# motorControllerMk3.net
KiCad netlist of a schematic drawn in EAGLE
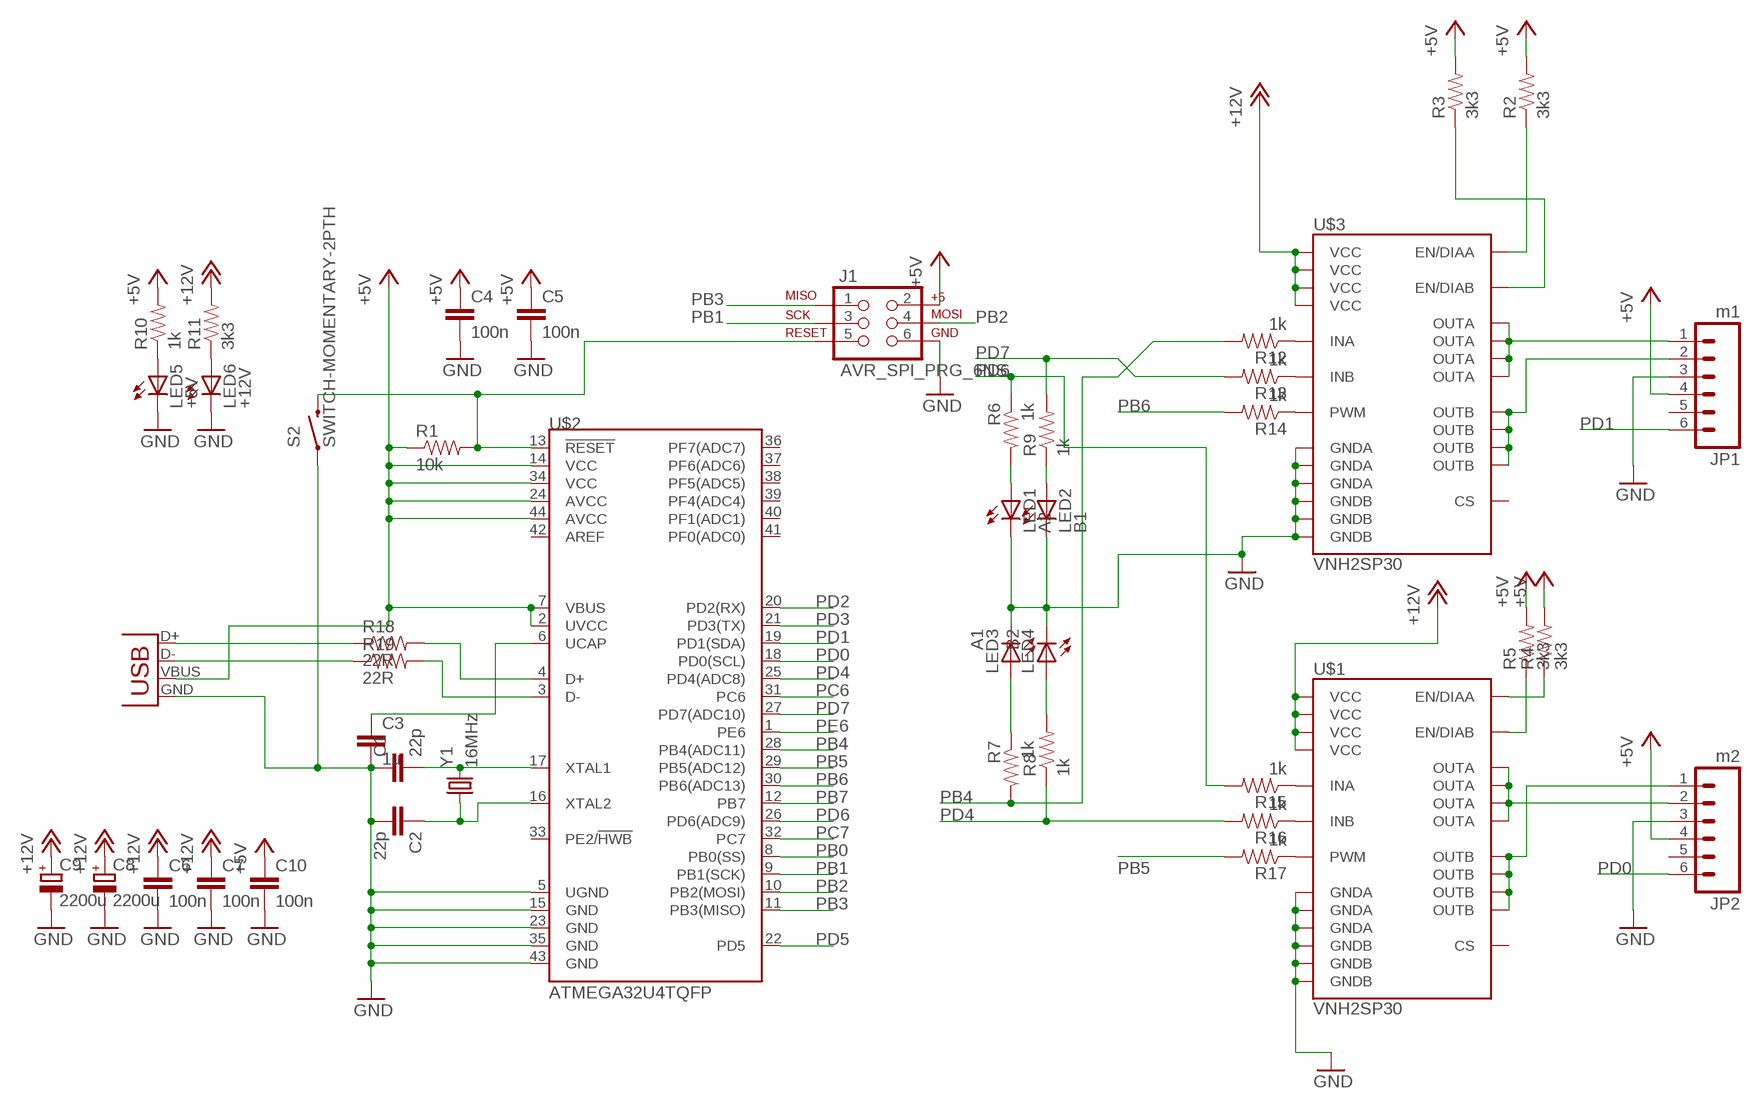
[diagram p0: schematic, sheet 1]

(export (version "E")
  (design (tool "Eeschema 10.0.6"))
  (components
    (comp (ref "C1")
      (value "22p")
      (footprint "eagle-import:0805")
      (libsource (lib "eagle-import") (part "CAP0805"))
    )
    (comp (ref "C2")
      (value "22p")
      (footprint "eagle-import:0805")
      (libsource (lib "eagle-import") (part "CAP0805"))
    )
    (comp (ref "C3")
      (value "1u")
      (footprint "eagle-import:0805")
      (libsource (lib "eagle-import") (part "CAP0805"))
    )
    (comp (ref "C4")
      (value "100n")
      (footprint "eagle-import:0805")
      (libsource (lib "eagle-import") (part "CAP0805"))
    )
    (comp (ref "C5")
      (value "100n")
      (footprint "eagle-import:0805")
      (libsource (lib "eagle-import") (part "CAP0805"))
    )
    (comp (ref "C6")
      (value "100n")
      (footprint "eagle-import:0805")
      (libsource (lib "eagle-import") (part "CAP0805"))
    )
    (comp (ref "C7")
      (value "100n")
      (footprint "eagle-import:0805")
      (libsource (lib "eagle-import") (part "CAP0805"))
    )
    (comp (ref "C8")
      (value "2200u")
      (footprint "eagle-import:E5-8,5")
      (libsource (lib "eagle-import") (part "CPOL-EUE5-8.5"))
    )
    (comp (ref "C9")
      (value "2200u")
      (footprint "eagle-import:E5-8,5")
      (libsource (lib "eagle-import") (part "CPOL-EUE5-8.5"))
    )
    (comp (ref "C10")
      (value "100n")
      (footprint "eagle-import:0805")
      (libsource (lib "eagle-import") (part "CAP0805"))
    )
    (comp (ref "J1")
      (value "AVR_SPI_PRG_6NS")
      (footprint "eagle-import:2X3-NS")
      (libsource (lib "eagle-import") (part "AVR_SPI_PRG_6NS"))
    )
    (comp (ref "JP1")
      (value "m1")
      (footprint "eagle-import:1X06")
      (libsource (lib "eagle-import") (part "M06SIP"))
    )
    (comp (ref "JP2")
      (value "m2")
      (footprint "eagle-import:1X06")
      (libsource (lib "eagle-import") (part "M06SIP"))
    )
    (comp (ref "JP3")
      (value "USB-SMD-NS")
      (footprint "eagle-import:USB-MINIB-NOSTOP")
      (libsource (lib "eagle-import") (part "USB-SMD-NS"))
    )
    (comp (ref "LED1")
      (value "A2")
      (footprint "eagle-import:LED-1206")
      (libsource (lib "eagle-import") (part "LED1206"))
    )
    (comp (ref "LED2")
      (value "B1")
      (footprint "eagle-import:LED-1206")
      (libsource (lib "eagle-import") (part "LED1206"))
    )
    (comp (ref "LED3")
      (value "A1")
      (footprint "eagle-import:LED-1206")
      (libsource (lib "eagle-import") (part "LED1206"))
    )
    (comp (ref "LED4")
      (value "B2")
      (footprint "eagle-import:LED-1206")
      (libsource (lib "eagle-import") (part "LED1206"))
    )
    (comp (ref "LED5")
      (value "+5V")
      (footprint "eagle-import:LED-1206")
      (libsource (lib "eagle-import") (part "LED1206"))
    )
    (comp (ref "LED6")
      (value "+12V")
      (footprint "eagle-import:LED-1206")
      (libsource (lib "eagle-import") (part "LED1206"))
    )
    (comp (ref "R1")
      (value "10k")
      (footprint "eagle-import:0805")
      (libsource (lib "eagle-import") (part "RESISTOR0805-RES"))
    )
    (comp (ref "R2")
      (value "3k3")
      (footprint "eagle-import:0805")
      (libsource (lib "eagle-import") (part "RESISTOR0805-RES"))
    )
    (comp (ref "R3")
      (value "3k3")
      (footprint "eagle-import:0805")
      (libsource (lib "eagle-import") (part "RESISTOR0805-RES"))
    )
    (comp (ref "R4")
      (value "3k3")
      (footprint "eagle-import:0805")
      (libsource (lib "eagle-import") (part "RESISTOR0805-RES"))
    )
    (comp (ref "R5")
      (value "3k3")
      (footprint "eagle-import:0805")
      (libsource (lib "eagle-import") (part "RESISTOR0805-RES"))
    )
    (comp (ref "R6")
      (value "1k")
      (footprint "eagle-import:0805")
      (libsource (lib "eagle-import") (part "RESISTOR0805-RES"))
    )
    (comp (ref "R7")
      (value "1k")
      (footprint "eagle-import:0805")
      (libsource (lib "eagle-import") (part "RESISTOR0805-RES"))
    )
    (comp (ref "R8")
      (value "1k")
      (footprint "eagle-import:0805")
      (libsource (lib "eagle-import") (part "RESISTOR0805-RES"))
    )
    (comp (ref "R9")
      (value "1k")
      (footprint "eagle-import:0805")
      (libsource (lib "eagle-import") (part "RESISTOR0805-RES"))
    )
    (comp (ref "R10")
      (value "1k")
      (footprint "eagle-import:0805")
      (libsource (lib "eagle-import") (part "RESISTOR0805-RES"))
    )
    (comp (ref "R11")
      (value "3k3")
      (footprint "eagle-import:0805")
      (libsource (lib "eagle-import") (part "RESISTOR0805-RES"))
    )
    (comp (ref "R12")
      (value "1k")
      (footprint "eagle-import:0805")
      (libsource (lib "eagle-import") (part "RESISTOR0805-RES"))
    )
    (comp (ref "R13")
      (value "1k")
      (footprint "eagle-import:0805")
      (libsource (lib "eagle-import") (part "RESISTOR0805-RES"))
    )
    (comp (ref "R14")
      (value "1k")
      (footprint "eagle-import:0805")
      (libsource (lib "eagle-import") (part "RESISTOR0805-RES"))
    )
    (comp (ref "R15")
      (value "1k")
      (footprint "eagle-import:0805")
      (libsource (lib "eagle-import") (part "RESISTOR0805-RES"))
    )
    (comp (ref "R16")
      (value "1k")
      (footprint "eagle-import:0805")
      (libsource (lib "eagle-import") (part "RESISTOR0805-RES"))
    )
    (comp (ref "R17")
      (value "1k")
      (footprint "eagle-import:0805")
      (libsource (lib "eagle-import") (part "RESISTOR0805-RES"))
    )
    (comp (ref "R18")
      (value "22R")
      (footprint "eagle-import:0805")
      (libsource (lib "eagle-import") (part "RESISTOR0805-RES"))
    )
    (comp (ref "R19")
      (value "22R")
      (footprint "eagle-import:0805")
      (libsource (lib "eagle-import") (part "RESISTOR0805-RES"))
    )
    (comp (ref "S2")
      (value "SWITCH-MOMENTARY-2PTH")
      (footprint "eagle-import:TACTILE-PTH")
      (libsource (lib "eagle-import") (part "SWITCH-MOMENTARY-2PTH"))
    )
    (comp (ref "U$1")
      (value "VNH2SP30")
      (footprint "eagle-import:VNH2SP30")
      (libsource (lib "eagle-import") (part "VNH2SP30"))
    )
    (comp (ref "U$2")
      (value "ATMEGA32U4TQFP")
      (footprint "eagle-import:SPARKFUN-DIGITALIC_TQFP44")
      (libsource (lib "eagle-import") (part "ATMEGA32U4TQFP"))
    )
    (comp (ref "U$3")
      (value "VNH2SP30")
      (footprint "eagle-import:VNH2SP30")
      (libsource (lib "eagle-import") (part "VNH2SP30"))
    )
    (comp (ref "Y1")
      (value "16MHz")
      (footprint "eagle-import:HC49US")
      (libsource (lib "eagle-import") (part "CRYSTALHC49US"))
    )
  )
  (nets
    (net (code "1") (name "+5V") (class "Default")
      (node (ref "C10") (pin "1") (pinfunction "1_1") (pintype "passive"))
      (node (ref "C4") (pin "1") (pinfunction "1_1") (pintype "passive"))
      (node (ref "C5") (pin "1") (pinfunction "1_1") (pintype "passive"))
      (node (ref "J1") (pin "2") (pinfunction "2_2") (pintype "passive"))
      (node (ref "JP1") (pin "4") (pinfunction "4_4") (pintype "passive"))
      (node (ref "JP2") (pin "4") (pinfunction "4_4") (pintype "passive"))
      (node (ref "JP3") (pin "VBUS") (pinfunction "VBUS_VBUS") (pintype "bidirectional"))
      (node (ref "R1") (pin "1") (pinfunction "1_1") (pintype "passive"))
      (node (ref "R10") (pin "2") (pinfunction "2_2") (pintype "passive"))
      (node (ref "R2") (pin "2") (pinfunction "2_2") (pintype "passive"))
      (node (ref "R3") (pin "2") (pinfunction "2_2") (pintype "passive"))
      (node (ref "R4") (pin "2") (pinfunction "2_2") (pintype "passive"))
      (node (ref "R5") (pin "2") (pinfunction "2_2") (pintype "passive"))
      (node (ref "U$2") (pin "14") (pinfunction "VCC_14") (pintype "bidirectional"))
      (node (ref "U$2") (pin "2") (pinfunction "UVCC_2") (pintype "bidirectional"))
      (node (ref "U$2") (pin "24") (pinfunction "AVCC_24") (pintype "bidirectional"))
      (node (ref "U$2") (pin "34") (pinfunction "VCC_34") (pintype "bidirectional"))
      (node (ref "U$2") (pin "44") (pinfunction "AVCC_44") (pintype "bidirectional"))
      (node (ref "U$2") (pin "7") (pinfunction "VBUS_7") (pintype "bidirectional"))
    )
    (net (code "2") (name "+12V") (class "Default")
      (node (ref "C6") (pin "1") (pinfunction "1_1") (pintype "passive"))
      (node (ref "C7") (pin "1") (pinfunction "1_1") (pintype "passive"))
      (node (ref "C8") (pin "+") (pinfunction "+_+") (pintype "passive"))
      (node (ref "C9") (pin "+") (pinfunction "+_+") (pintype "passive"))
      (node (ref "R11") (pin "2") (pinfunction "2_2") (pintype "passive"))
      (node (ref "U$1") (pin "13") (pinfunction "VCC_13") (pintype "bidirectional"))
      (node (ref "U$1") (pin "23") (pinfunction "VCC_23") (pintype "bidirectional"))
      (node (ref "U$1") (pin "3") (pinfunction "VCC_3") (pintype "bidirectional"))
      (node (ref "U$1") (pin "SLUG1") (pinfunction "VCC_SLUG1") (pintype "bidirectional"))
      (node (ref "U$3") (pin "13") (pinfunction "VCC_13") (pintype "bidirectional"))
      (node (ref "U$3") (pin "23") (pinfunction "VCC_23") (pintype "bidirectional"))
      (node (ref "U$3") (pin "3") (pinfunction "VCC_3") (pintype "bidirectional"))
      (node (ref "U$3") (pin "SLUG1") (pinfunction "VCC_SLUG1") (pintype "bidirectional"))
    )
    (net (code "3") (name "/PB0") (class "Default")
      (node (ref "U$2") (pin "8") (pinfunction "PB0(SS)_8") (pintype "bidirectional"))
    )
    (net (code "4") (name "/PB1") (class "Default")
      (node (ref "J1") (pin "3") (pinfunction "3_3") (pintype "passive"))
      (node (ref "U$2") (pin "9") (pinfunction "PB1(SCK)_9") (pintype "bidirectional"))
    )
    (net (code "5") (name "/PB2") (class "Default")
      (node (ref "J1") (pin "4") (pinfunction "4_4") (pintype "passive"))
      (node (ref "U$2") (pin "10") (pinfunction "PB2(MOSI)_10") (pintype "bidirectional"))
    )
    (net (code "6") (name "/PB3") (class "Default")
      (node (ref "J1") (pin "1") (pinfunction "1_1") (pintype "passive"))
      (node (ref "U$2") (pin "11") (pinfunction "PB3(MISO)_11") (pintype "bidirectional"))
    )
    (net (code "7") (name "/PB4") (class "Default")
      (node (ref "R12") (pin "2") (pinfunction "2_2") (pintype "passive"))
      (node (ref "R7") (pin "2") (pinfunction "2_2") (pintype "passive"))
      (node (ref "U$2") (pin "28") (pinfunction "PB4(ADC11)_28") (pintype "bidirectional"))
    )
    (net (code "8") (name "/PB5") (class "Default")
      (node (ref "R17") (pin "2") (pinfunction "2_2") (pintype "passive"))
      (node (ref "U$2") (pin "29") (pinfunction "PB5(ADC12)_29") (pintype "bidirectional"))
    )
    (net (code "9") (name "/PB6") (class "Default")
      (node (ref "R14") (pin "2") (pinfunction "2_2") (pintype "passive"))
      (node (ref "U$2") (pin "30") (pinfunction "PB6(ADC13)_30") (pintype "bidirectional"))
    )
    (net (code "10") (name "/PB7") (class "Default")
      (node (ref "U$2") (pin "12") (pinfunction "PB7_12") (pintype "bidirectional"))
    )
    (net (code "11") (name "/PC6") (class "Default")
      (node (ref "U$2") (pin "31") (pinfunction "PC6_31") (pintype "bidirectional"))
    )
    (net (code "12") (name "/PC7") (class "Default")
      (node (ref "U$2") (pin "32") (pinfunction "PC7_32") (pintype "bidirectional"))
    )
    (net (code "13") (name "/PD0") (class "Default")
      (node (ref "JP2") (pin "6") (pinfunction "6_6") (pintype "passive"))
      (node (ref "U$2") (pin "18") (pinfunction "PD0(SCL)_18") (pintype "bidirectional"))
    )
    (net (code "14") (name "/PD1") (class "Default")
      (node (ref "JP1") (pin "6") (pinfunction "6_6") (pintype "passive"))
      (node (ref "U$2") (pin "19") (pinfunction "PD1(SDA)_19") (pintype "bidirectional"))
    )
    (net (code "15") (name "/PD2") (class "Default")
      (node (ref "U$2") (pin "20") (pinfunction "PD2(RX)_20") (pintype "bidirectional"))
    )
    (net (code "16") (name "/PD3") (class "Default")
      (node (ref "U$2") (pin "21") (pinfunction "PD3(TX)_21") (pintype "bidirectional"))
    )
    (net (code "17") (name "/PD4") (class "Default")
      (node (ref "R16") (pin "2") (pinfunction "2_2") (pintype "passive"))
      (node (ref "R8") (pin "1") (pinfunction "1_1") (pintype "passive"))
      (node (ref "U$2") (pin "25") (pinfunction "PD4(ADC8)_25") (pintype "bidirectional"))
    )
    (net (code "18") (name "/PD5") (class "Default")
      (node (ref "U$2") (pin "22") (pinfunction "PD5_22") (pintype "bidirectional"))
    )
    (net (code "19") (name "/PD6") (class "Default")
      (node (ref "R15") (pin "2") (pinfunction "2_2") (pintype "passive"))
      (node (ref "R6") (pin "1") (pinfunction "1_1") (pintype "passive"))
      (node (ref "U$2") (pin "26") (pinfunction "PD6(ADC9)_26") (pintype "bidirectional"))
    )
    (net (code "20") (name "/PD7") (class "Default")
      (node (ref "R13") (pin "2") (pinfunction "2_2") (pintype "passive"))
      (node (ref "R9") (pin "2") (pinfunction "2_2") (pintype "passive"))
      (node (ref "U$2") (pin "27") (pinfunction "PD7(ADC10)_27") (pintype "bidirectional"))
    )
    (net (code "21") (name "/PE6") (class "Default")
      (node (ref "U$2") (pin "1") (pinfunction "PE6_1") (pintype "bidirectional"))
    )
    (net (code "22") (name "GND") (class "Default")
      (node (ref "C1") (pin "1") (pinfunction "1_1") (pintype "passive"))
      (node (ref "C10") (pin "2") (pinfunction "2_2") (pintype "passive"))
      (node (ref "C2") (pin "2") (pinfunction "2_2") (pintype "passive"))
      (node (ref "C3") (pin "2") (pinfunction "2_2") (pintype "passive"))
      (node (ref "C4") (pin "2") (pinfunction "2_2") (pintype "passive"))
      (node (ref "C5") (pin "2") (pinfunction "2_2") (pintype "passive"))
      (node (ref "C6") (pin "2") (pinfunction "2_2") (pintype "passive"))
      (node (ref "C7") (pin "2") (pinfunction "2_2") (pintype "passive"))
      (node (ref "C8") (pin "-") (pinfunction "-_-") (pintype "passive"))
      (node (ref "C9") (pin "-") (pinfunction "-_-") (pintype "passive"))
      (node (ref "J1") (pin "6") (pinfunction "6_6") (pintype "passive"))
      (node (ref "JP1") (pin "3") (pinfunction "3_3") (pintype "passive"))
      (node (ref "JP2") (pin "3") (pinfunction "3_3") (pintype "passive"))
      (node (ref "JP3") (pin "GND") (pinfunction "GND_GND") (pintype "bidirectional"))
      (node (ref "LED1") (pin "C") (pinfunction "C_C") (pintype "passive"))
      (node (ref "LED2") (pin "C") (pinfunction "C_C") (pintype "passive"))
      (node (ref "LED3") (pin "C") (pinfunction "C_C") (pintype "passive"))
      (node (ref "LED4") (pin "C") (pinfunction "C_C") (pintype "passive"))
      (node (ref "LED5") (pin "C") (pinfunction "C_C") (pintype "passive"))
      (node (ref "LED6") (pin "C") (pinfunction "C_C") (pintype "passive"))
      (node (ref "S2") (pin "1") (pinfunction "1_1") (pintype "passive"))
      (node (ref "U$1") (pin "18") (pinfunction "GNDB_18") (pintype "bidirectional"))
      (node (ref "U$1") (pin "19") (pinfunction "GNDB_19") (pintype "bidirectional"))
      (node (ref "U$1") (pin "20") (pinfunction "GNDB_20") (pintype "bidirectional"))
      (node (ref "U$1") (pin "26") (pinfunction "GNDA_26") (pintype "bidirectional"))
      (node (ref "U$1") (pin "27") (pinfunction "GNDA_27") (pintype "bidirectional"))
      (node (ref "U$1") (pin "28") (pinfunction "GNDA_28") (pintype "bidirectional"))
      (node (ref "U$2") (pin "15") (pinfunction "GND_15") (pintype "bidirectional"))
      (node (ref "U$2") (pin "23") (pinfunction "GND_23") (pintype "bidirectional"))
      (node (ref "U$2") (pin "35") (pinfunction "GND_35") (pintype "bidirectional"))
      (node (ref "U$2") (pin "43") (pinfunction "GND_43") (pintype "bidirectional"))
      (node (ref "U$2") (pin "5") (pinfunction "UGND_5") (pintype "bidirectional"))
      (node (ref "U$3") (pin "18") (pinfunction "GNDB_18") (pintype "bidirectional"))
      (node (ref "U$3") (pin "19") (pinfunction "GNDB_19") (pintype "bidirectional"))
      (node (ref "U$3") (pin "20") (pinfunction "GNDB_20") (pintype "bidirectional"))
      (node (ref "U$3") (pin "26") (pinfunction "GNDA_26") (pintype "bidirectional"))
      (node (ref "U$3") (pin "27") (pinfunction "GNDA_27") (pintype "bidirectional"))
      (node (ref "U$3") (pin "28") (pinfunction "GNDA_28") (pintype "bidirectional"))
    )
    (net (code "23") (name "Net-(JP1-Pad1)") (class "Default")
      (node (ref "JP1") (pin "1") (pinfunction "1_1") (pintype "passive"))
      (node (ref "U$3") (pin "1") (pinfunction "OUTA_1") (pintype "bidirectional"))
      (node (ref "U$3") (pin "25") (pinfunction "OUTA_25") (pintype "bidirectional"))
      (node (ref "U$3") (pin "30") (pinfunction "OUTA_30") (pintype "bidirectional"))
      (node (ref "U$3") (pin "SLUG3") (pinfunction "OUTA_SLUG3") (pintype "bidirectional"))
    )
    (net (code "24") (name "Net-(JP1-Pad2)") (class "Default")
      (node (ref "JP1") (pin "2") (pinfunction "2_2") (pintype "passive"))
      (node (ref "U$3") (pin "15") (pinfunction "OUTB_15") (pintype "bidirectional"))
      (node (ref "U$3") (pin "16") (pinfunction "OUTB_16") (pintype "bidirectional"))
      (node (ref "U$3") (pin "21") (pinfunction "OUTB_21") (pintype "bidirectional"))
      (node (ref "U$3") (pin "SLUG2") (pinfunction "OUTB_SLUG2") (pintype "bidirectional"))
    )
    (net (code "25") (name "Net-(JP2-Pad1)") (class "Default")
      (node (ref "JP2") (pin "1") (pinfunction "1_1") (pintype "passive"))
      (node (ref "U$1") (pin "15") (pinfunction "OUTB_15") (pintype "bidirectional"))
      (node (ref "U$1") (pin "16") (pinfunction "OUTB_16") (pintype "bidirectional"))
      (node (ref "U$1") (pin "21") (pinfunction "OUTB_21") (pintype "bidirectional"))
      (node (ref "U$1") (pin "SLUG2") (pinfunction "OUTB_SLUG2") (pintype "bidirectional"))
    )
    (net (code "26") (name "Net-(JP2-Pad2)") (class "Default")
      (node (ref "JP2") (pin "2") (pinfunction "2_2") (pintype "passive"))
      (node (ref "U$1") (pin "1") (pinfunction "OUTA_1") (pintype "bidirectional"))
      (node (ref "U$1") (pin "25") (pinfunction "OUTA_25") (pintype "bidirectional"))
      (node (ref "U$1") (pin "30") (pinfunction "OUTA_30") (pintype "bidirectional"))
      (node (ref "U$1") (pin "SLUG3") (pinfunction "OUTA_SLUG3") (pintype "bidirectional"))
    )
    (net (code "27") (name "Net-(JP3-PadD+)") (class "Default")
      (node (ref "JP3") (pin "D+") (pinfunction "D+_D+") (pintype "bidirectional"))
      (node (ref "R18") (pin "1") (pinfunction "1_1") (pintype "passive"))
    )
    (net (code "28") (name "Net-(JP3-PadD-)") (class "Default")
      (node (ref "JP3") (pin "D-") (pinfunction "D-_D-") (pintype "bidirectional"))
      (node (ref "R19") (pin "1") (pinfunction "1_1") (pintype "passive"))
    )
    (net (code "29") (name "Net-(LED1-PadA)") (class "Default")
      (node (ref "LED1") (pin "A") (pinfunction "A_A") (pintype "passive"))
      (node (ref "R6") (pin "2") (pinfunction "2_2") (pintype "passive"))
    )
    (net (code "30") (name "Net-(LED2-PadA)") (class "Default")
      (node (ref "LED2") (pin "A") (pinfunction "A_A") (pintype "passive"))
      (node (ref "R9") (pin "1") (pinfunction "1_1") (pintype "passive"))
    )
    (net (code "31") (name "Net-(LED3-PadA)") (class "Default")
      (node (ref "LED3") (pin "A") (pinfunction "A_A") (pintype "passive"))
      (node (ref "R7") (pin "1") (pinfunction "1_1") (pintype "passive"))
    )
    (net (code "32") (name "Net-(LED4-PadA)") (class "Default")
      (node (ref "LED4") (pin "A") (pinfunction "A_A") (pintype "passive"))
      (node (ref "R8") (pin "2") (pinfunction "2_2") (pintype "passive"))
    )
    (net (code "33") (name "Net-(LED5-PadA)") (class "Default")
      (node (ref "LED5") (pin "A") (pinfunction "A_A") (pintype "passive"))
      (node (ref "R10") (pin "1") (pinfunction "1_1") (pintype "passive"))
    )
    (net (code "34") (name "Net-(LED6-PadA)") (class "Default")
      (node (ref "LED6") (pin "A") (pinfunction "A_A") (pintype "passive"))
      (node (ref "R11") (pin "1") (pinfunction "1_1") (pintype "passive"))
    )
    (net (code "35") (name "Net-(S2-2)") (class "Default")
      (node (ref "J1") (pin "5") (pinfunction "5_5") (pintype "passive"))
      (node (ref "R1") (pin "2") (pinfunction "2_2") (pintype "passive"))
      (node (ref "S2") (pin "3") (pinfunction "2_3") (pintype "passive"))
      (node (ref "U$2") (pin "13") (pinfunction "~{RESET}_13") (pintype "bidirectional"))
    )
    (net (code "36") (name "Net-(U$1-EN{slash}DIAA)") (class "Default")
      (node (ref "R4") (pin "1") (pinfunction "1_1") (pintype "passive"))
      (node (ref "U$1") (pin "6") (pinfunction "EN/DIAA_6") (pintype "bidirectional"))
    )
    (net (code "37") (name "Net-(U$1-EN{slash}DIAB)") (class "Default")
      (node (ref "R5") (pin "1") (pinfunction "1_1") (pintype "passive"))
      (node (ref "U$1") (pin "10") (pinfunction "EN/DIAB_10") (pintype "bidirectional"))
    )
    (net (code "38") (name "Net-(U$1-INA)") (class "Default")
      (node (ref "R15") (pin "1") (pinfunction "1_1") (pintype "passive"))
      (node (ref "U$1") (pin "5") (pinfunction "INA_5") (pintype "bidirectional"))
    )
    (net (code "39") (name "Net-(U$1-INB)") (class "Default")
      (node (ref "R16") (pin "1") (pinfunction "1_1") (pintype "passive"))
      (node (ref "U$1") (pin "11") (pinfunction "INB_11") (pintype "bidirectional"))
    )
    (net (code "40") (name "Net-(U$1-PWM)") (class "Default")
      (node (ref "R17") (pin "1") (pinfunction "1_1") (pintype "passive"))
      (node (ref "U$1") (pin "8") (pinfunction "PWM_8") (pintype "bidirectional"))
    )
    (net (code "41") (name "Net-(U$2-D+)") (class "Default")
      (node (ref "R18") (pin "2") (pinfunction "2_2") (pintype "passive"))
      (node (ref "U$2") (pin "4") (pinfunction "D+_4") (pintype "bidirectional"))
    )
    (net (code "42") (name "Net-(U$2-D-)") (class "Default")
      (node (ref "R19") (pin "2") (pinfunction "2_2") (pintype "passive"))
      (node (ref "U$2") (pin "3") (pinfunction "D-_3") (pintype "bidirectional"))
    )
    (net (code "43") (name "Net-(U$2-UCAP)") (class "Default")
      (node (ref "C3") (pin "1") (pinfunction "1_1") (pintype "passive"))
      (node (ref "U$2") (pin "6") (pinfunction "UCAP_6") (pintype "bidirectional"))
    )
    (net (code "44") (name "Net-(U$2-XTAL1)") (class "Default")
      (node (ref "C1") (pin "2") (pinfunction "2_2") (pintype "passive"))
      (node (ref "U$2") (pin "17") (pinfunction "XTAL1_17") (pintype "bidirectional"))
      (node (ref "Y1") (pin "2") (pinfunction "2_2") (pintype "passive"))
    )
    (net (code "45") (name "Net-(U$2-XTAL2)") (class "Default")
      (node (ref "C2") (pin "1") (pinfunction "1_1") (pintype "passive"))
      (node (ref "U$2") (pin "16") (pinfunction "XTAL2_16") (pintype "bidirectional"))
      (node (ref "Y1") (pin "1") (pinfunction "1_1") (pintype "passive"))
    )
    (net (code "46") (name "Net-(U$3-EN{slash}DIAA)") (class "Default")
      (node (ref "R2") (pin "1") (pinfunction "1_1") (pintype "passive"))
      (node (ref "U$3") (pin "6") (pinfunction "EN/DIAA_6") (pintype "bidirectional"))
    )
    (net (code "47") (name "Net-(U$3-EN{slash}DIAB)") (class "Default")
      (node (ref "R3") (pin "1") (pinfunction "1_1") (pintype "passive"))
      (node (ref "U$3") (pin "10") (pinfunction "EN/DIAB_10") (pintype "bidirectional"))
    )
    (net (code "48") (name "Net-(U$3-INA)") (class "Default")
      (node (ref "R12") (pin "1") (pinfunction "1_1") (pintype "passive"))
      (node (ref "U$3") (pin "5") (pinfunction "INA_5") (pintype "bidirectional"))
    )
    (net (code "49") (name "Net-(U$3-INB)") (class "Default")
      (node (ref "R13") (pin "1") (pinfunction "1_1") (pintype "passive"))
      (node (ref "U$3") (pin "11") (pinfunction "INB_11") (pintype "bidirectional"))
    )
    (net (code "50") (name "Net-(U$3-PWM)") (class "Default")
      (node (ref "R14") (pin "1") (pinfunction "1_1") (pintype "passive"))
      (node (ref "U$3") (pin "8") (pinfunction "PWM_8") (pintype "bidirectional"))
    )
    (net (code "51") (name "unconnected-(JP1-Pad5)") (class "Default")
      (node (ref "JP1") (pin "5") (pinfunction "5_5") (pintype "passive"))
    )
    (net (code "52") (name "unconnected-(JP2-Pad5)") (class "Default")
      (node (ref "JP2") (pin "5") (pinfunction "5_5") (pintype "passive"))
    )
    (net (code "53") (name "unconnected-(U$1-CS-Pad9)") (class "Default")
      (node (ref "U$1") (pin "9") (pinfunction "CS_9") (pintype "bidirectional"))
    )
    (net (code "54") (name "unconnected-(U$2-AREF-Pad42)") (class "Default")
      (node (ref "U$2") (pin "42") (pinfunction "AREF_42") (pintype "bidirectional"))
    )
    (net (code "55") (name "unconnected-(U$2-PE2{slash}~{HWB}-Pad33)") (class "Default")
      (node (ref "U$2") (pin "33") (pinfunction "PE2/~{HWB}_33") (pintype "bidirectional"))
    )
    (net (code "56") (name "unconnected-(U$2-PF0(ADC0)-Pad41)") (class "Default")
      (node (ref "U$2") (pin "41") (pinfunction "PF0(ADC0)_41") (pintype "bidirectional"))
    )
    (net (code "57") (name "unconnected-(U$2-PF1(ADC1)-Pad40)") (class "Default")
      (node (ref "U$2") (pin "40") (pinfunction "PF1(ADC1)_40") (pintype "bidirectional"))
    )
    (net (code "58") (name "unconnected-(U$2-PF4(ADC4)-Pad39)") (class "Default")
      (node (ref "U$2") (pin "39") (pinfunction "PF4(ADC4)_39") (pintype "bidirectional"))
    )
    (net (code "59") (name "unconnected-(U$2-PF5(ADC5)-Pad38)") (class "Default")
      (node (ref "U$2") (pin "38") (pinfunction "PF5(ADC5)_38") (pintype "bidirectional"))
    )
    (net (code "60") (name "unconnected-(U$2-PF6(ADC6)-Pad37)") (class "Default")
      (node (ref "U$2") (pin "37") (pinfunction "PF6(ADC6)_37") (pintype "bidirectional"))
    )
    (net (code "61") (name "unconnected-(U$2-PF7(ADC7)-Pad36)") (class "Default")
      (node (ref "U$2") (pin "36") (pinfunction "PF7(ADC7)_36") (pintype "bidirectional"))
    )
    (net (code "62") (name "unconnected-(U$3-CS-Pad9)") (class "Default")
      (node (ref "U$3") (pin "9") (pinfunction "CS_9") (pintype "bidirectional"))
    )
  )
)
